# ArduinoUnoShield.net
KiCad netlist of a schematic drawn in Altium Designer
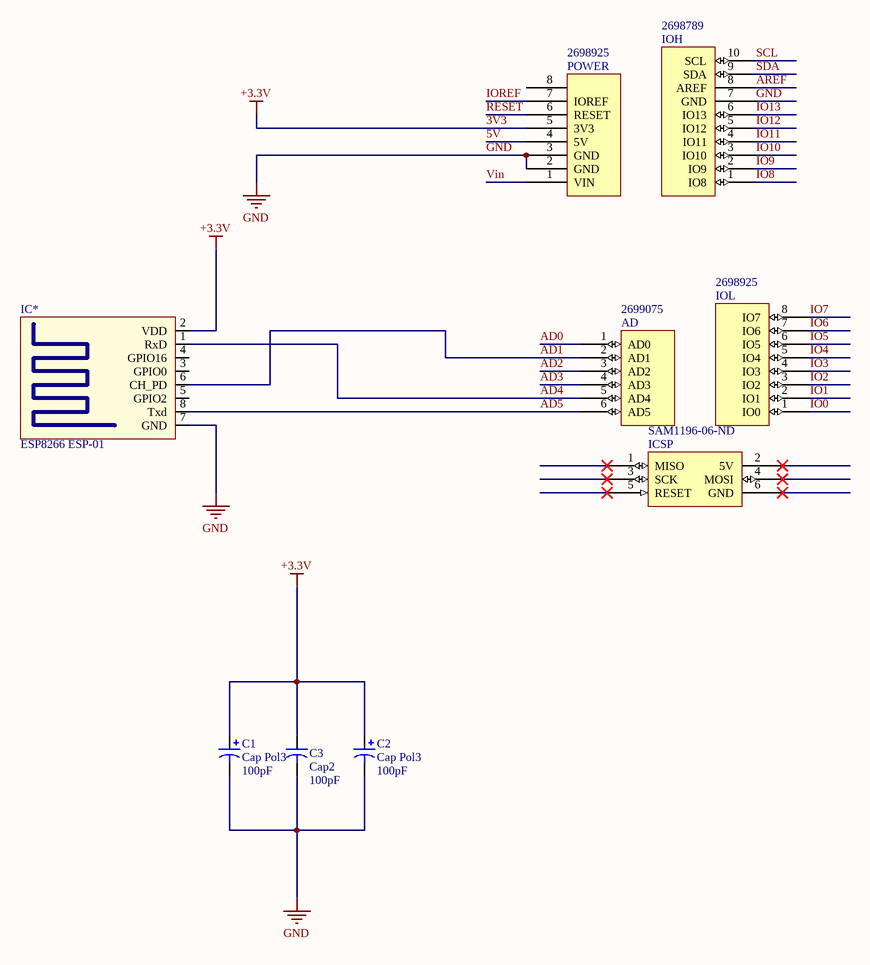
[diagram p0: ArduinoUnoShield.SchDoc]

(export (version "E")
  (design (tool "Eeschema 10.0.6"))
  (components
    (comp (ref "AD")
      (value "AD")
      (footprint "Header:Header 6x1 8.5mm")
      (fields (field (name "SUPPLIER PART NUMBER 4") "2699075"))
      (libsource (lib "Header") (part "AD"))
    )
    (comp (ref "C1")
      (value "Cap Pol3")
      (footprint "C0805")
      (description "Polarized Capacitor (Surface Mount)")
      (fields (field (name "ALTIUM_VALUE") "100pF") (field (name "PUBLISHER") "Altium Limited"))
      (libsource (lib "Miscellaneous Devices") (part "Cap Pol3"))
    )
    (comp (ref "C2")
      (value "Cap Pol3")
      (footprint "C0805")
      (description "Polarized Capacitor (Surface Mount)")
      (fields (field (name "ALTIUM_VALUE") "100pF") (field (name "PUBLISHER") "Altium Limited"))
      (libsource (lib "Miscellaneous Devices") (part "Cap Pol3"))
    )
    (comp (ref "C3")
      (value "Cap2")
      (footprint "CAPR5-4X5")
      (description "Capacitor")
      (fields (field (name "ALTIUM_VALUE") "100pF") (field (name "PUBLISHER") "Altium Limited"))
      (libsource (lib "Miscellaneous Devices") (part "Cap2"))
    )
    (comp (ref "IC*")
      (value "ESP8266 ESP-01")
      (footprint "ESP8266 ESP-01")
      (libsource (lib "ESP8266") (part "ESP8266 ESP-01"))
    )
    (comp (ref "ICSP")
      (value "ICSP")
      (footprint "ICSP")
      (fields (field (name "SUPPLIER PART NUMBER 5") "SAM1196-06-ND"))
      (libsource (lib "Header") (part "ICSP"))
    )
    (comp (ref "IOH")
      (value "IOH")
      (footprint "Header:Header 10x1 8.5mm")
      (fields (field (name "SUPPLIER PART NUMBER 3") "2698789"))
      (libsource (lib "Header") (part "IOH"))
    )
    (comp (ref "IOL")
      (value "IOL")
      (footprint "Header 8x1 8.5mm")
      (fields (field (name "SUPPLIER PART NUMBER 4") "2698925"))
      (libsource (lib "Header") (part "IOL"))
    )
    (comp (ref "POWER")
      (value "POWER_UNO")
      (footprint "Header 8x1 8.5mm")
      (fields (field (name "SUPPLIER PART NUMBER 4") "2698925"))
      (libsource (lib "Header") (part "POWER_UNO"))
    )
  )
  (nets
    (net (code "1") (name "+3.3V") (class "Default")
      (node (ref "C1") (pin "1") (pinfunction "1_1") (pintype "passive"))
      (node (ref "C2") (pin "1") (pinfunction "1_1") (pintype "passive"))
      (node (ref "C3") (pin "1") (pinfunction "1_1") (pintype "passive"))
      (node (ref "IC*") (pin "2") (pinfunction "VDD_2") (pintype "passive"))
      (node (ref "POWER") (pin "5") (pinfunction "3V3_5") (pintype "power_in"))
    )
    (net (code "2") (name "/5V") (class "Default")
      (node (ref "POWER") (pin "4") (pinfunction "5V_4") (pintype "power_in"))
    )
    (net (code "4") (name "/AD0") (class "Default")
      (node (ref "AD") (pin "1") (pinfunction "AD0_1") (pintype "bidirectional"))
    )
    (net (code "5") (name "/AD1") (class "Default")
      (node (ref "AD") (pin "2") (pinfunction "AD1_2") (pintype "bidirectional"))
      (node (ref "IC*") (pin "6") (pinfunction "CH_PD_6") (pintype "passive"))
    )
    (net (code "6") (name "/AD2") (class "Default")
      (node (ref "AD") (pin "3") (pinfunction "AD2_3") (pintype "bidirectional"))
    )
    (net (code "7") (name "/AD3") (class "Default")
      (node (ref "AD") (pin "4") (pinfunction "AD3_4") (pintype "bidirectional"))
    )
    (net (code "8") (name "/AD4") (class "Default")
      (node (ref "AD") (pin "5") (pinfunction "AD4_5") (pintype "bidirectional"))
      (node (ref "IC*") (pin "1") (pinfunction "RxD_1") (pintype "passive"))
    )
    (net (code "9") (name "/AD5") (class "Default")
      (node (ref "AD") (pin "6") (pinfunction "AD5_6") (pintype "bidirectional"))
      (node (ref "IC*") (pin "8") (pinfunction "Txd_8") (pintype "passive"))
    )
    (net (code "10") (name "/AREF") (class "Default")
      (node (ref "IOH") (pin "8") (pinfunction "AREF_8") (pintype "passive"))
    )
    (net (code "11") (name "/IO0") (class "Default")
      (node (ref "IOL") (pin "1") (pinfunction "IO0_1") (pintype "bidirectional"))
    )
    (net (code "12") (name "/IO1") (class "Default")
      (node (ref "IOL") (pin "2") (pinfunction "IO1_2") (pintype "bidirectional"))
    )
    (net (code "13") (name "/IO2") (class "Default")
      (node (ref "IOL") (pin "3") (pinfunction "IO2_3") (pintype "bidirectional"))
    )
    (net (code "14") (name "/IO3") (class "Default")
      (node (ref "IOL") (pin "4") (pinfunction "IO3_4") (pintype "bidirectional"))
    )
    (net (code "15") (name "/IO4") (class "Default")
      (node (ref "IOL") (pin "5") (pinfunction "IO4_5") (pintype "bidirectional"))
    )
    (net (code "16") (name "/IO5") (class "Default")
      (node (ref "IOL") (pin "6") (pinfunction "IO5_6") (pintype "bidirectional"))
    )
    (net (code "17") (name "/IO6") (class "Default")
      (node (ref "IOL") (pin "7") (pinfunction "IO6_7") (pintype "bidirectional"))
    )
    (net (code "18") (name "/IO7") (class "Default")
      (node (ref "IOL") (pin "8") (pinfunction "IO7_8") (pintype "bidirectional"))
    )
    (net (code "19") (name "/IO8") (class "Default")
      (node (ref "IOH") (pin "1") (pinfunction "IO8_1") (pintype "bidirectional"))
    )
    (net (code "20") (name "/IO9") (class "Default")
      (node (ref "IOH") (pin "2") (pinfunction "IO9_2") (pintype "bidirectional"))
    )
    (net (code "21") (name "/IO10") (class "Default")
      (node (ref "IOH") (pin "3") (pinfunction "IO10_3") (pintype "bidirectional"))
    )
    (net (code "22") (name "/IO11") (class "Default")
      (node (ref "IOH") (pin "4") (pinfunction "IO11_4") (pintype "bidirectional"))
    )
    (net (code "23") (name "/IO12") (class "Default")
      (node (ref "IOH") (pin "5") (pinfunction "IO12_5") (pintype "bidirectional"))
    )
    (net (code "24") (name "/IO13") (class "Default")
      (node (ref "IOH") (pin "6") (pinfunction "IO13_6") (pintype "bidirectional"))
    )
    (net (code "25") (name "/IOREF") (class "Default")
      (node (ref "POWER") (pin "7") (pinfunction "IOREF_7") (pintype "power_in"))
    )
    (net (code "26") (name "/RESET") (class "Default")
      (node (ref "POWER") (pin "6") (pinfunction "RESET_6") (pintype "passive"))
    )
    (net (code "27") (name "/SCL") (class "Default")
      (node (ref "IOH") (pin "10") (pinfunction "SCL_10") (pintype "bidirectional"))
    )
    (net (code "28") (name "/SDA") (class "Default")
      (node (ref "IOH") (pin "9") (pinfunction "SDA_9") (pintype "bidirectional"))
    )
    (net (code "29") (name "/Vin") (class "Default")
      (node (ref "POWER") (pin "1") (pinfunction "VIN_1") (pintype "power_in"))
    )
    (net (code "30") (name "GND") (class "Default")
      (node (ref "C1") (pin "2") (pinfunction "2_2") (pintype "passive"))
      (node (ref "C2") (pin "2") (pinfunction "2_2") (pintype "passive"))
      (node (ref "C3") (pin "2") (pinfunction "2_2") (pintype "passive"))
      (node (ref "IC*") (pin "7") (pinfunction "GND_7") (pintype "passive"))
      (node (ref "IOH") (pin "7") (pinfunction "GND_7") (pintype "power_in"))
      (node (ref "POWER") (pin "2") (pinfunction "GND_2") (pintype "power_in"))
      (node (ref "POWER") (pin "3") (pinfunction "GND_3") (pintype "power_in"))
    )
    (net (code "31") (name "unconnected-(IC*-GPIO0-Pad3)") (class "Default")
      (node (ref "IC*") (pin "3") (pinfunction "GPIO0_3") (pintype "passive"))
    )
    (net (code "32") (name "unconnected-(IC*-GPIO2-Pad5)") (class "Default")
      (node (ref "IC*") (pin "5") (pinfunction "GPIO2_5") (pintype "passive"))
    )
    (net (code "33") (name "unconnected-(IC*-GPIO16-Pad4)") (class "Default")
      (node (ref "IC*") (pin "4") (pinfunction "GPIO16_4") (pintype "passive"))
    )
    (net (code "34") (name "unconnected-(ICSP-5V-Pad2)") (class "Default")
      (node (ref "ICSP") (pin "2") (pinfunction "5V_2") (pintype "power_in+no_connect"))
    )
    (net (code "35") (name "unconnected-(ICSP-GND-Pad6)") (class "Default")
      (node (ref "ICSP") (pin "6") (pinfunction "GND_6") (pintype "power_in+no_connect"))
    )
    (net (code "36") (name "unconnected-(ICSP-MISO-Pad1)") (class "Default")
      (node (ref "ICSP") (pin "1") (pinfunction "MISO_1") (pintype "bidirectional+no_connect"))
    )
    (net (code "37") (name "unconnected-(ICSP-MOSI-Pad4)") (class "Default")
      (node (ref "ICSP") (pin "4") (pinfunction "MOSI_4") (pintype "bidirectional+no_connect"))
    )
    (net (code "38") (name "unconnected-(ICSP-RESET-Pad5)") (class "Default")
      (node (ref "ICSP") (pin "5") (pinfunction "RESET_5") (pintype "input+no_connect"))
    )
    (net (code "39") (name "unconnected-(ICSP-SCK-Pad3)") (class "Default")
      (node (ref "ICSP") (pin "3") (pinfunction "SCK_3") (pintype "bidirectional+no_connect"))
    )
    (net (code "40") (name "unconnected-(POWER-Pad8)") (class "Default")
      (node (ref "POWER") (pin "8") (pintype "passive"))
    )
  )
)
